# Power.net
KiCad netlist of a schematic drawn in Altium Designer
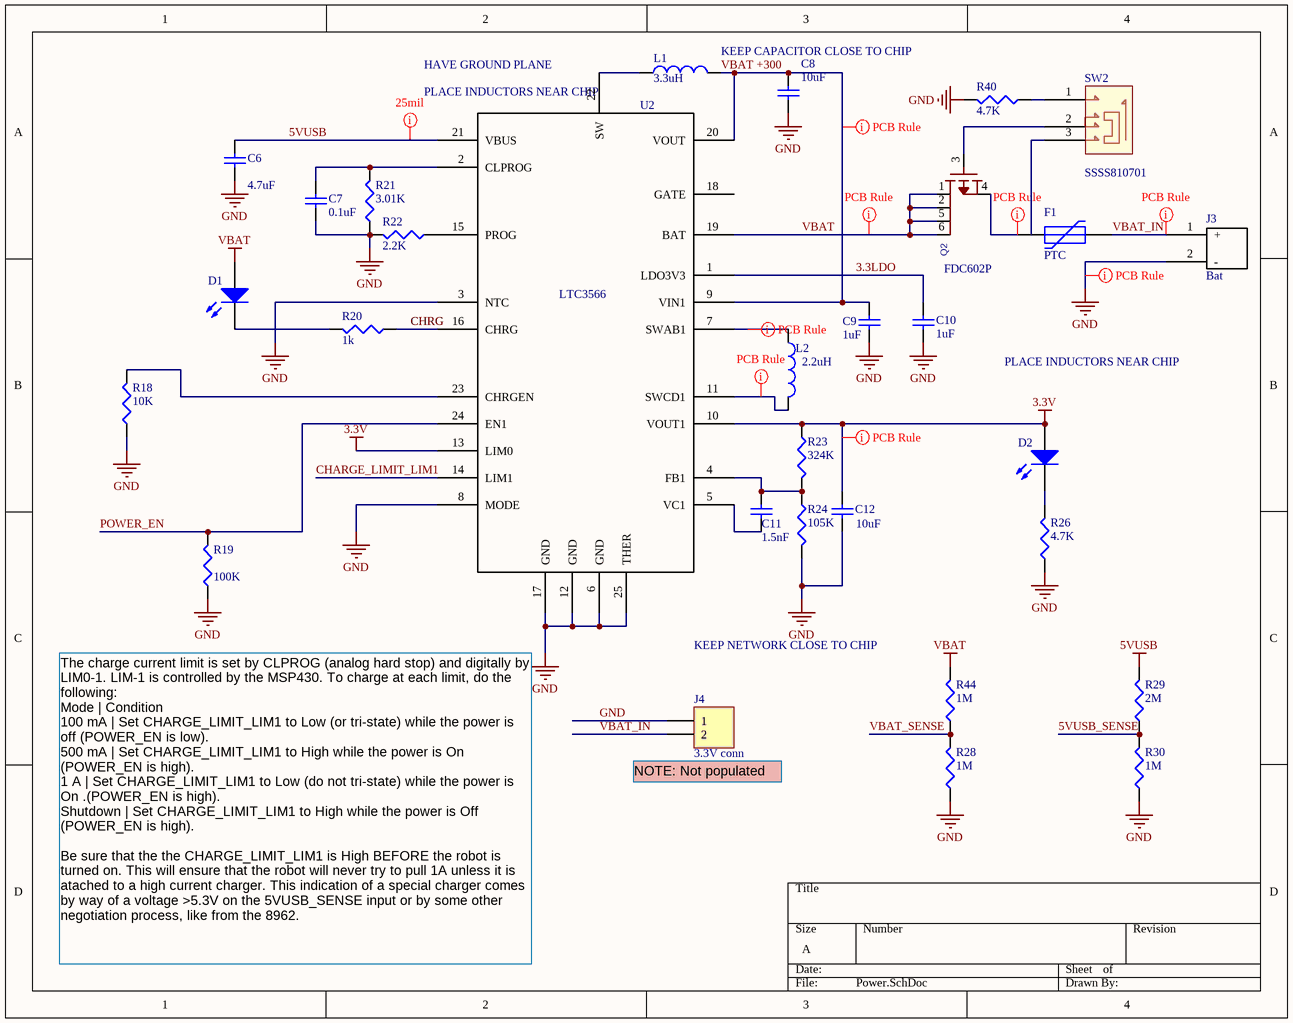
[diagram p0: Power.SchDoc]

(export (version "E")
  (design (tool "Eeschema 10.0.6"))
  (components
    (comp (ref "C6")
      (value "4.7uF")
      (footprint "CAPC1608L")
      (description "Capacitor (Semiconductor SIM Model)")
      (fields
        (field (name "PART NUMBER") "JMK107BJ475KA-T")
        (field (name "MANUFACTURER") "Taiyo Yuden")
        (field (name "PUBLISHER") "Altium Limited")
      )
      (libsource (lib "Miscellaneous Devices") (part "Cap Semi"))
    )
    (comp (ref "C7")
      (value "0.1uF")
      (footprint "CAPC1005L")
      (description "Capacitor")
      (fields
        (field (name "PART NUMBER") "GRM155R71C104KA88D")
        (field (name "MANUFACTURER") "Murata")
        (field (name "PUBLISHER") "Altium Limited")
      )
      (libsource (lib "Miscellaneous Devices") (part "Cap"))
    )
    (comp (ref "C8")
      (value "10uF")
      (footprint "CAPC1608L")
      (description "Capacitor")
      (fields
        (field (name "PART NUMBER") "GRM188R60J106ME47J")
        (field (name "MANUFACTURER") "Murata")
        (field (name "PUBLISHER") "Altium Limited")
      )
      (libsource (lib "Miscellaneous Devices") (part "Cap"))
    )
    (comp (ref "C9")
      (value "1uF")
      (footprint "CAPC1608L")
      (description "Capacitor")
      (fields
        (field (name "PART NUMBER") "LMK107B7105KA-T")
        (field (name "MANUFACTURER") "Taiyo Yuden")
        (field (name "PUBLISHER") "Altium Limited")
      )
      (libsource (lib "Miscellaneous Devices") (part "Cap"))
    )
    (comp (ref "C10")
      (value "1uF")
      (footprint "CAPC1608L")
      (description "Capacitor")
      (fields
        (field (name "PART NUMBER") "LMK107B7105KA-T")
        (field (name "MANUFACTURER") "Taiyo Yuden")
        (field (name "PUBLISHER") "Altium Limited")
      )
      (libsource (lib "Miscellaneous Devices") (part "Cap"))
    )
    (comp (ref "C11")
      (value "1.5nF")
      (footprint "CAPC1005L")
      (description "Capacitor")
      (fields
        (field (name "PART NUMBER") "GRM155R71H152KA01D")
        (field (name "MANUFACTURER") "Murata")
        (field (name "PUBLISHER") "Altium Limited")
      )
      (libsource (lib "Miscellaneous Devices") (part "Cap"))
    )
    (comp (ref "C12")
      (value "10uF")
      (footprint "CAPC1608L")
      (description "Capacitor")
      (fields
        (field (name "PART NUMBER") "GRM188R60J106ME47J")
        (field (name "MANUFACTURER") "Murata")
        (field (name "PUBLISHER") "Altium Limited")
      )
      (libsource (lib "Miscellaneous Devices") (part "Cap"))
    )
    (comp (ref "D1")
      (value "Charge")
      (footprint "INDC2012L")
      (description "Typical RED, GREEN, YELLOW, AMBER GaAs LED")
      (fields
        (field (name "PART NUMBER") "LTST-C190AKT")
        (field (name "MANUFACTURER") "Lite-on")
        (field (name "PUBLISHER") "Altium Limited")
      )
      (libsource (lib "Miscellaneous Devices") (part "LED2"))
    )
    (comp (ref "D2")
      (value "Power")
      (footprint "INDC2012L")
      (description "Typical RED, GREEN, YELLOW, AMBER GaAs LED")
      (fields
        (field (name "PART NUMBER") "LS Q976-nR-1")
        (field (name "MANUFACTURER") "Osram")
        (field (name "PUBLISHER") "Altium Limited")
      )
      (libsource (lib "Miscellaneous Devices") (part "LED2"))
    )
    (comp (ref "F1")
      (value "PTC")
      (footprint "ERJ8G-1206")
      (description "Fuse")
      (fields
        (field (name "PART NUMBER") "MF-NSMF200-2")
        (field (name "MANUFACTURER") "Bourns")
        (field (name "PUBLISHER") "Altium Limited")
      )
      (libsource (lib "mrone") (part "PTC_FUSE"))
    )
    (comp (ref "J3")
      (value "Bat")
      (footprint "BatteryConnJST")
      (fields (field (name "PART NUMBER") "B2B-PH-K-S(LF)(SN)") (field (name "MANUFACTURER") "JST"))
      (libsource (lib "mrone") (part "BatteryConnJST"))
    )
    (comp (ref "J4")
      (value "3.3V conn")
      (footprint "HDR1X2")
      (description "Header, 2-Pin")
      (fields (field (name "PUBLISHER") "Altium Limited"))
      (libsource (lib "Miscellaneous Connectors") (part "Header 2"))
    )
    (comp (ref "L1")
      (value "3.3uH")
      (footprint "IndPow")
      (fields (field (name "PART NUMBER") "LPS 4018-332MLB") (field (name "MANUFACTURER") "Coilcraft"))
      (libsource (lib "mrone") (part "Inductor"))
    )
    (comp (ref "L2")
      (value "2.2uH")
      (footprint "IndPow")
      (fields (field (name "PART NUMBER") "LPS 4018-222MLB") (field (name "MANUFACTURER") "Coilcraft"))
      (libsource (lib "mrone") (part "Inductor"))
    )
    (comp (ref "Q2")
      (value "Q_MOSFETP4D_SOT23-6")
      (footprint "SOT23-6")
      (fields (field (name "PART NUMBER") "FDC602P") (field (name "MANUFACTURER") "Fairchild"))
      (libsource (lib "UnifiedLibraryDBlib") (part "Q_MOSFETP4D_SOT23-6"))
    )
    (comp (ref "R18")
      (value "10K")
      (footprint "RESC1608L")
      (description "Resistor")
      (fields
        (field (name "PART NUMBER") "71-CRCW0603-10K-E3")
        (field (name "MANUFACTURER") "Vishay Dale")
        (field (name "PUBLISHER") "Altium Limited")
      )
      (libsource (lib "Miscellaneous Devices") (part "Res3"))
    )
    (comp (ref "R19")
      (value "100K")
      (footprint "RESC1608L")
      (description "Resistor")
      (fields
        (field (name "PART NUMBER") "ERJ-3GEYJ104V")
        (field (name "MANUFACTURER") "Panasonic")
        (field (name "PUBLISHER") "Altium Limited")
      )
      (libsource (lib "Miscellaneous Devices") (part "Res3"))
    )
    (comp (ref "R20")
      (value "1k")
      (footprint "RESC1608L")
      (description "Resistor")
      (fields
        (field (name "PART NUMBER") "ERJ-3GEYJ102V")
        (field (name "MANUFACTURER") "Panasonic")
        (field (name "PUBLISHER") "Altium Limited")
      )
      (libsource (lib "Miscellaneous Devices") (part "Res3"))
    )
    (comp (ref "R21")
      (value "3.01K")
      (footprint "RESC1608L")
      (description "Resistor")
      (fields
        (field (name "PART NUMBER") "RMCF0603FT3K01")
        (field (name "MANUFACTURER") "Stackpole")
        (field (name "PUBLISHER") "Altium Limited")
      )
      (libsource (lib "Miscellaneous Devices") (part "Res3"))
    )
    (comp (ref "R22")
      (value "2.2K")
      (footprint "RESC1608L")
      (description "Resistor")
      (fields
        (field (name "PART NUMBER") "ERJ-3GEYJ-222V")
        (field (name "MANUFACTURER") "Panasonic")
        (field (name "PUBLISHER") "Altium Limited")
      )
      (libsource (lib "Miscellaneous Devices") (part "Res3"))
    )
    (comp (ref "R23")
      (value "324K")
      (footprint "RESC1608L")
      (description "Resistor")
      (fields
        (field (name "PART NUMBER") "RC0603FR-07324KL")
        (field (name "MANUFACTURER") "Yageo")
        (field (name "PUBLISHER") "Altium Limited")
      )
      (libsource (lib "Miscellaneous Devices") (part "Res3"))
    )
    (comp (ref "R24")
      (value "105K")
      (footprint "RESC1608L")
      (description "Resistor")
      (fields
        (field (name "PART NUMBER") "RMCF 1/16 105K 1% R")
        (field (name "MANUFACTURER") "Stackpole")
        (field (name "PUBLISHER") "Altium Limited")
      )
      (libsource (lib "Miscellaneous Devices") (part "Res3"))
    )
    (comp (ref "R26")
      (value "4.7K")
      (footprint "RESC1608L")
      (description "Resistor")
      (fields
        (field (name "PART NUMBER") "ERJ-3GEYJ472V")
        (field (name "MANUFACTURER") "Panasonic")
        (field (name "PUBLISHER") "Altium Limited")
      )
      (libsource (lib "Miscellaneous Devices") (part "Res3"))
    )
    (comp (ref "R28")
      (value "1M")
      (footprint "RESC1608L")
      (description "Resistor")
      (fields
        (field (name "PART NUMBER") "ERJ-3GEY-J105V")
        (field (name "MANUFACTURER") "Panasonic")
        (field (name "PUBLISHER") "Altium Limited")
      )
      (libsource (lib "Miscellaneous Devices") (part "Res3"))
    )
    (comp (ref "R29")
      (value "2M")
      (footprint "RESC1608L")
      (description "Resistor")
      (fields
        (field (name "PART NUMBER") "ERJ-3GEY-J205V")
        (field (name "MANUFACTURER") "Panasonic")
        (field (name "PUBLISHER") "Altium Limited")
      )
      (libsource (lib "Miscellaneous Devices") (part "Res3"))
    )
    (comp (ref "R30")
      (value "1M")
      (footprint "RESC1608L")
      (description "Resistor")
      (fields
        (field (name "PART NUMBER") "ERJ-3GEY-J205V")
        (field (name "MANUFACTURER") "Panasonic")
        (field (name "PUBLISHER") "Altium Limited")
      )
      (libsource (lib "Miscellaneous Devices") (part "Res3"))
    )
    (comp (ref "R40")
      (value "4.7K")
      (footprint "RESC1608L")
      (description "Resistor")
      (fields
        (field (name "PART NUMBER") "ERJ-3GEYJ472V")
        (field (name "MANUFACTURER") "Panasonic")
        (field (name "PUBLISHER") "Altium Limited")
      )
      (libsource (lib "Miscellaneous Devices") (part "Res3"))
    )
    (comp (ref "R44")
      (value "1M")
      (footprint "RESC1608L")
      (description "Resistor")
      (fields
        (field (name "PART NUMBER") "ERJ-3GEY-J105V")
        (field (name "MANUFACTURER") "Panasonic")
        (field (name "PUBLISHER") "Altium Limited")
      )
      (libsource (lib "Miscellaneous Devices") (part "Res3"))
    )
    (comp (ref "SW2")
      (value "S_SSSS810701_SSSS810701")
      (footprint "SSSS810701")
      (description "SSSS810701")
      (fields (field (name "PART NUMBER") "SSSS810701") (field (name "MANUFACTURER") "Alps"))
      (libsource (lib "Schlib1") (part "S_SSSS810701_SSSS810701"))
    )
    (comp (ref "U2")
      (value "LTC3566")
      (footprint "QFN-24")
      (fields (field (name "PART NUMBER") "LTC3566EUF#PBF") (field (name "MANUFACTURER") "Linear"))
      (libsource (lib "Schematic Components") (part "LTC3566"))
    )
  )
  (nets
    (net (code "1") (name "/3.3LDO") (class "Default")
      (node (ref "C10") (pin "1") (pinfunction "1_1") (pintype "passive"))
      (node (ref "U2") (pin "1") (pinfunction "LDO3V3_1") (pintype "passive"))
    )
    (net (code "2") (name "/5VUSB_SENSE") (class "Default")
      (node (ref "R29") (pin "1") (pinfunction "1_1") (pintype "passive"))
      (node (ref "R30") (pin "2") (pinfunction "2_2") (pintype "passive"))
    )
    (net (code "3") (name "/CHARGE_LIMIT_LIM1") (class "Default")
      (node (ref "U2") (pin "14") (pinfunction "LIM1_14") (pintype "passive"))
    )
    (net (code "4") (name "/CHRG") (class "Default")
      (node (ref "R20") (pin "1") (pinfunction "1_1") (pintype "passive"))
      (node (ref "U2") (pin "16") (pinfunction "CHRG_16") (pintype "passive"))
    )
    (net (code "5") (name "/POWER_EN") (class "Default")
      (node (ref "R19") (pin "2") (pinfunction "2_2") (pintype "passive"))
      (node (ref "U2") (pin "24") (pinfunction "EN1_24") (pintype "passive"))
    )
    (net (code "6") (name "/VBAT +300") (class "Default")
      (node (ref "C8") (pin "2") (pinfunction "2_2") (pintype "passive"))
      (node (ref "C9") (pin "1") (pinfunction "1_1") (pintype "passive"))
      (node (ref "L1") (pin "2") (pinfunction "2_2") (pintype "passive"))
      (node (ref "U2") (pin "20") (pinfunction "VOUT_20") (pintype "passive"))
      (node (ref "U2") (pin "9") (pinfunction "VIN1_9") (pintype "passive"))
    )
    (net (code "7") (name "/VBAT_IN") (class "Default")
      (node (ref "F1") (pin "2") (pinfunction "2_2") (pintype "passive"))
      (node (ref "J3") (pin "1") (pinfunction "+_1") (pintype "passive"))
      (node (ref "J4") (pin "2") (pinfunction "2_2") (pintype "passive"))
    )
    (net (code "8") (name "/VBAT_SENSE") (class "Default")
      (node (ref "R28") (pin "2") (pinfunction "2_2") (pintype "passive"))
      (node (ref "R44") (pin "1") (pinfunction "1_1") (pintype "passive"))
    )
    (net (code "9") (name "3.3V") (class "Default")
      (node (ref "C12") (pin "2") (pinfunction "2_2") (pintype "passive"))
      (node (ref "D2") (pin "1") (pinfunction "A_1") (pintype "passive"))
      (node (ref "R23") (pin "1") (pinfunction "1_1") (pintype "passive"))
      (node (ref "U2") (pin "10") (pinfunction "VOUT1_10") (pintype "passive"))
      (node (ref "U2") (pin "13") (pinfunction "LIM0_13") (pintype "passive"))
    )
    (net (code "10") (name "5VUSB") (class "Default")
      (node (ref "C6") (pin "2") (pinfunction "2_2") (pintype "passive"))
      (node (ref "R29") (pin "2") (pinfunction "2_2") (pintype "passive"))
      (node (ref "U2") (pin "21") (pinfunction "VBUS_21") (pintype "passive"))
    )
    (net (code "11") (name "GND") (class "Default")
      (node (ref "C10") (pin "2") (pinfunction "2_2") (pintype "passive"))
      (node (ref "C12") (pin "1") (pinfunction "1_1") (pintype "passive"))
      (node (ref "C6") (pin "1") (pinfunction "1_1") (pintype "passive"))
      (node (ref "C7") (pin "1") (pinfunction "1_1") (pintype "passive"))
      (node (ref "C8") (pin "1") (pinfunction "1_1") (pintype "passive"))
      (node (ref "C9") (pin "2") (pinfunction "2_2") (pintype "passive"))
      (node (ref "J3") (pin "2") (pinfunction "-_2") (pintype "passive"))
      (node (ref "J4") (pin "1") (pinfunction "1_1") (pintype "passive"))
      (node (ref "R18") (pin "1") (pinfunction "1_1") (pintype "passive"))
      (node (ref "R19") (pin "1") (pinfunction "1_1") (pintype "passive"))
      (node (ref "R21") (pin "1") (pinfunction "1_1") (pintype "passive"))
      (node (ref "R22") (pin "2") (pinfunction "2_2") (pintype "passive"))
      (node (ref "R24") (pin "2") (pinfunction "2_2") (pintype "passive"))
      (node (ref "R26") (pin "1") (pinfunction "1_1") (pintype "passive"))
      (node (ref "R28") (pin "1") (pinfunction "1_1") (pintype "passive"))
      (node (ref "R30") (pin "1") (pinfunction "1_1") (pintype "passive"))
      (node (ref "R40") (pin "2") (pinfunction "2_2") (pintype "passive"))
      (node (ref "U2") (pin "12") (pinfunction "GND_12") (pintype "passive"))
      (node (ref "U2") (pin "17") (pinfunction "GND_17") (pintype "passive"))
      (node (ref "U2") (pin "25") (pinfunction "THER_25") (pintype "passive"))
      (node (ref "U2") (pin "3") (pinfunction "NTC_3") (pintype "passive"))
      (node (ref "U2") (pin "6") (pinfunction "GND_6") (pintype "passive"))
      (node (ref "U2") (pin "8") (pinfunction "MODE_8") (pintype "passive"))
    )
    (net (code "12") (name "Net-(D1-K)") (class "Default")
      (node (ref "D1") (pin "2") (pinfunction "K_2") (pintype "passive"))
      (node (ref "R20") (pin "2") (pinfunction "2_2") (pintype "passive"))
    )
    (net (code "13") (name "Net-(D2-K)") (class "Default")
      (node (ref "D2") (pin "2") (pinfunction "K_2") (pintype "passive"))
      (node (ref "R26") (pin "2") (pinfunction "2_2") (pintype "passive"))
    )
    (net (code "14") (name "Net-(Q2-G)") (class "Default")
      (node (ref "Q2") (pin "3") (pinfunction "G_3") (pintype "passive"))
      (node (ref "SW2") (pin "2") (pintype "passive"))
    )
    (net (code "15") (name "Net-(Q2-S)") (class "Default")
      (node (ref "F1") (pin "1") (pinfunction "1_1") (pintype "passive"))
      (node (ref "Q2") (pin "4") (pinfunction "S_4") (pintype "passive"))
    )
    (net (code "16") (name "Net-(R40-Pad1)") (class "Default")
      (node (ref "R40") (pin "1") (pinfunction "1_1") (pintype "passive"))
      (node (ref "SW2") (pin "1") (pintype "passive"))
    )
    (net (code "17") (name "Net-(U2-CHRGEN)") (class "Default")
      (node (ref "R18") (pin "2") (pinfunction "2_2") (pintype "passive"))
      (node (ref "U2") (pin "23") (pinfunction "CHRGEN_23") (pintype "passive"))
    )
    (net (code "18") (name "Net-(U2-CLPROG)") (class "Default")
      (node (ref "C7") (pin "2") (pinfunction "2_2") (pintype "passive"))
      (node (ref "R21") (pin "2") (pinfunction "2_2") (pintype "passive"))
      (node (ref "U2") (pin "2") (pinfunction "CLPROG_2") (pintype "passive"))
    )
    (net (code "19") (name "Net-(U2-FB1)") (class "Default")
      (node (ref "C11") (pin "1") (pinfunction "1_1") (pintype "passive"))
      (node (ref "R23") (pin "2") (pinfunction "2_2") (pintype "passive"))
      (node (ref "R24") (pin "1") (pinfunction "1_1") (pintype "passive"))
      (node (ref "U2") (pin "4") (pinfunction "FB1_4") (pintype "passive"))
    )
    (net (code "20") (name "Net-(U2-PROG)") (class "Default")
      (node (ref "R22") (pin "1") (pinfunction "1_1") (pintype "passive"))
      (node (ref "U2") (pin "15") (pinfunction "PROG_15") (pintype "passive"))
    )
    (net (code "21") (name "Net-(U2-SW)") (class "Default")
      (node (ref "L1") (pin "1") (pinfunction "1_1") (pintype "passive"))
      (node (ref "U2") (pin "22") (pinfunction "SW_22") (pintype "passive"))
    )
    (net (code "22") (name "Net-(U2-SWAB1)") (class "Default")
      (node (ref "L2") (pin "1") (pinfunction "1_1") (pintype "passive"))
      (node (ref "U2") (pin "7") (pinfunction "SWAB1_7") (pintype "passive"))
    )
    (net (code "23") (name "Net-(U2-SWCD1)") (class "Default")
      (node (ref "L2") (pin "2") (pinfunction "2_2") (pintype "passive"))
      (node (ref "U2") (pin "11") (pinfunction "SWCD1_11") (pintype "passive"))
    )
    (net (code "24") (name "Net-(U2-VC1)") (class "Default")
      (node (ref "C11") (pin "2") (pinfunction "2_2") (pintype "passive"))
      (node (ref "U2") (pin "5") (pinfunction "VC1_5") (pintype "passive"))
    )
    (net (code "25") (name "VBAT") (class "Default")
      (node (ref "D1") (pin "1") (pinfunction "A_1") (pintype "passive"))
      (node (ref "Q2") (pin "1") (pinfunction "D_1") (pintype "passive"))
      (node (ref "Q2") (pin "2") (pinfunction "D_2") (pintype "passive"))
      (node (ref "Q2") (pin "5") (pinfunction "D_5") (pintype "passive"))
      (node (ref "Q2") (pin "6") (pinfunction "D_6") (pintype "passive"))
      (node (ref "R44") (pin "2") (pinfunction "2_2") (pintype "passive"))
      (node (ref "U2") (pin "19") (pinfunction "BAT_19") (pintype "passive"))
    )
    (net (code "26") (name "unconnected-(SW2-Pad3)") (class "Default")
      (node (ref "SW2") (pin "3") (pintype "passive"))
    )
    (net (code "27") (name "unconnected-(U2-GATE-Pad18)") (class "Default")
      (node (ref "U2") (pin "18") (pinfunction "GATE_18") (pintype "passive"))
    )
  )
)
